# mainboard_v2_0.net
KiCad netlist of a schematic drawn in EAGLE
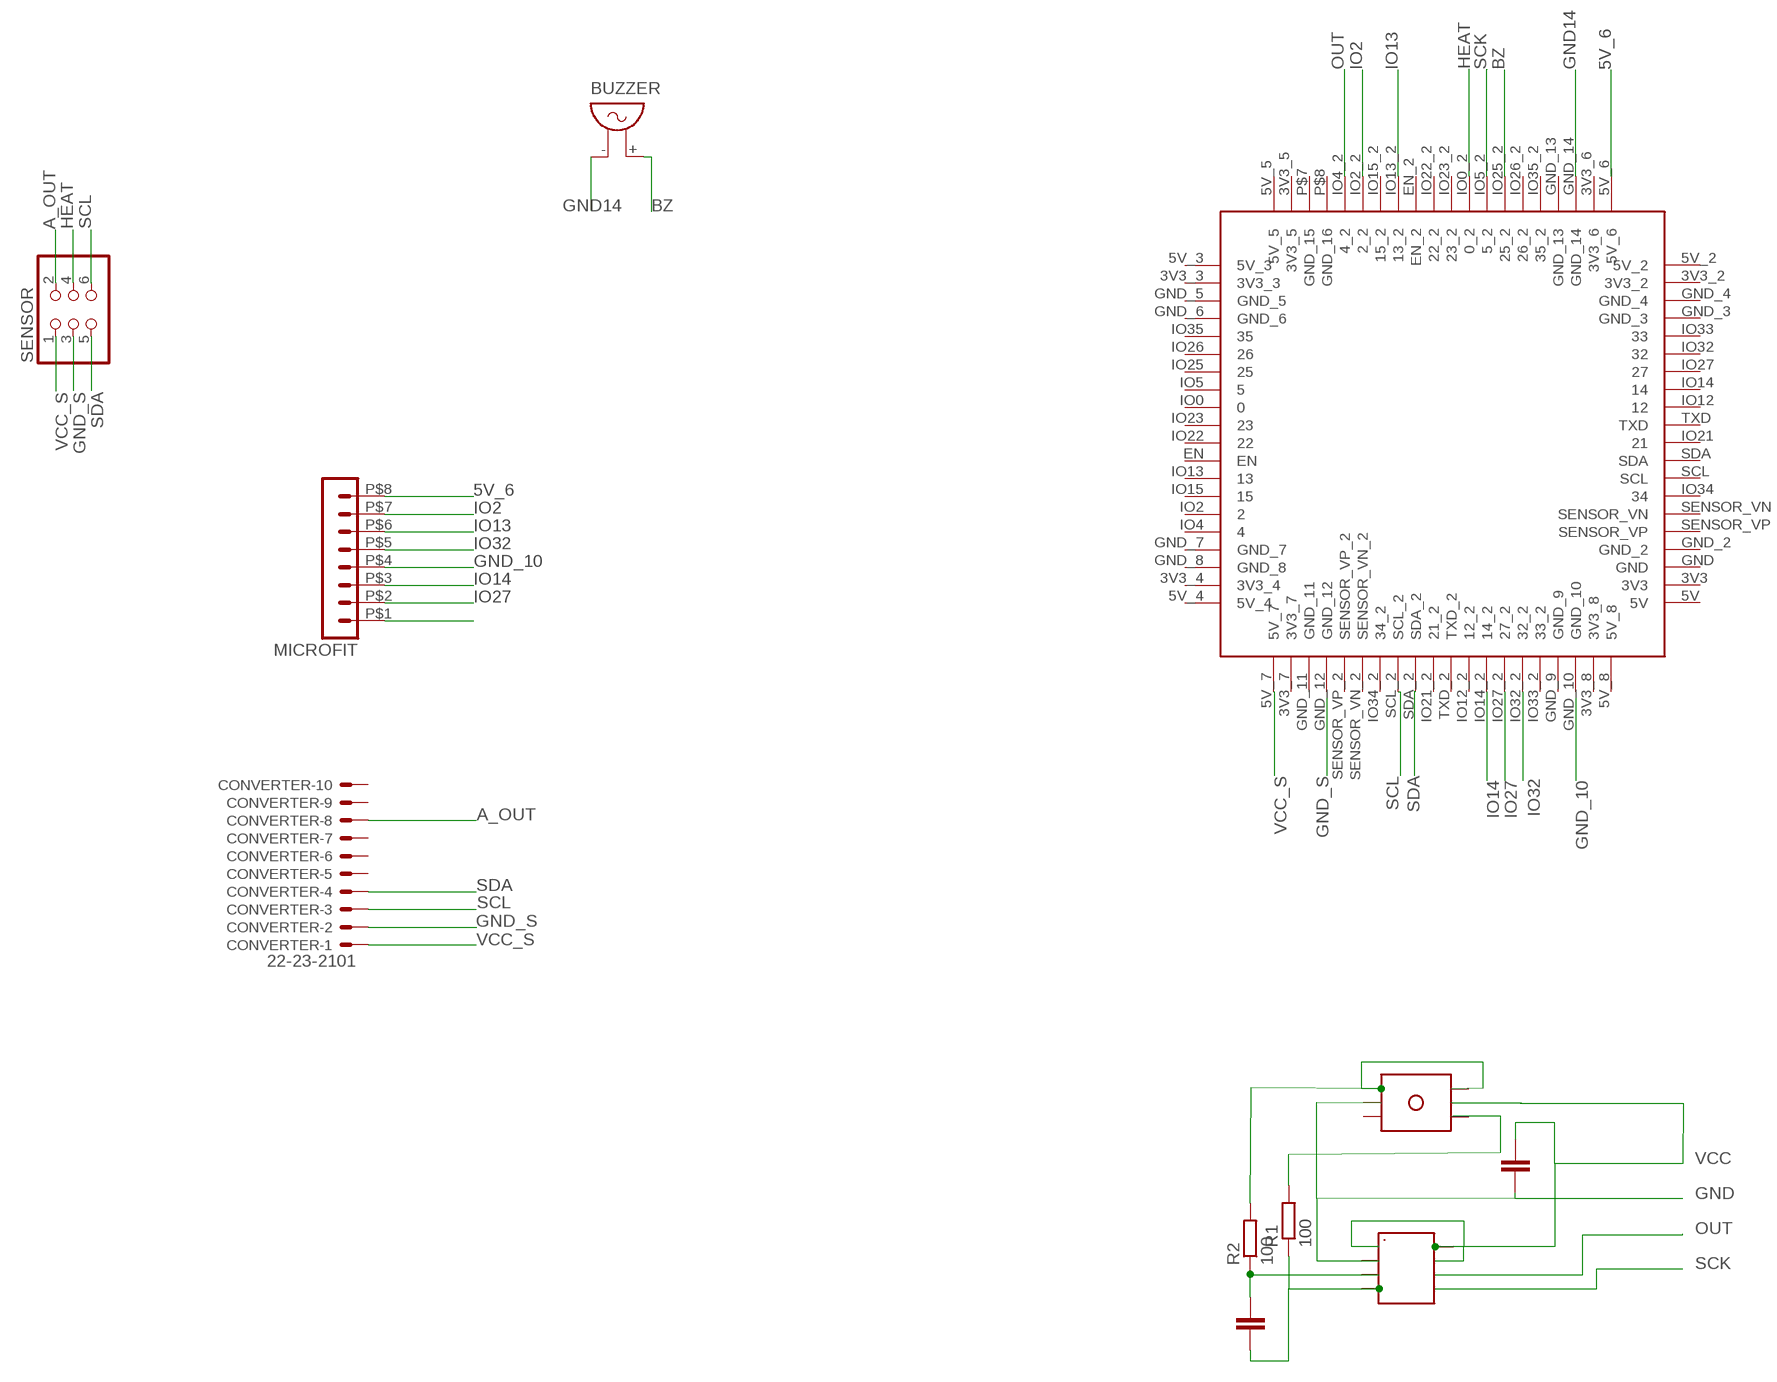
[diagram p0: schematic, sheet 1]

(export (version "E")
  (design (tool "Eeschema 10.0.6"))
  (components
    (comp (ref "BUZZER")
      (value "F/QMX")
      (footprint "eagle-import:F_QMX")
      (libsource (lib "eagle-import") (part "F/QMX"))
    )
    (comp (ref "C1")
      (value "100n")
      (footprint "eagle-import:C0805")
      (libsource (lib "eagle-import") (part "C-EUC0805"))
    )
    (comp (ref "C2")
      (value "100n")
      (footprint "eagle-import:C0805")
      (libsource (lib "eagle-import") (part "C-EUC0805"))
    )
    (comp (ref "CONVERTER")
      (value "22-23-2101")
      (footprint "eagle-import:22-23-2101")
      (fields (field (name "MF") "MOLEX"))
      (libsource (lib "eagle-import") (part "22-23-2101"))
    )
    (comp (ref "MICROFIT")
      (value "HEADER_POS8_43045-0800")
      (footprint "eagle-import:43045-0800")
      (libsource (lib "eagle-import") (part "HEADER_POS8_?43045-0800"))
    )
    (comp (ref "R1")
      (value "100")
      (footprint "eagle-import:R0805")
      (libsource (lib "eagle-import") (part "R-EU_R0805"))
    )
    (comp (ref "R2")
      (value "100")
      (footprint "eagle-import:R0805")
      (libsource (lib "eagle-import") (part "R-EU_R0805"))
    )
    (comp (ref "SENSOR")
      (value "PINHD-2X3")
      (footprint "eagle-import:2X03")
      (libsource (lib "eagle-import") (part "PINHD-2X3"))
    )
    (comp (ref "U$1")
      (value "WT32_SC01WT32_D")
      (footprint "eagle-import:WT32_DUPLICATED")
      (libsource (lib "eagle-import") (part "WT32_SC01WT32_D"))
    )
    (comp (ref "U$2")
      (value "HX710B")
      (footprint "eagle-import:HX710B_SMD")
      (libsource (lib "eagle-import") (part "HX710B"))
    )
    (comp (ref "U$3")
      (value "PRESSUREPRESSURE_PTH")
      (footprint "eagle-import:PRESSURE_PTH")
      (libsource (lib "eagle-import") (part "PRESSUREPRESSURE_PTH"))
    )
  )
  (nets
    (net (code "1") (name "/5V_6") (class "Default")
      (node (ref "MICROFIT") (pin "P$8") (pinfunction "8_P$8") (pintype "passive"))
      (node (ref "U$1") (pin "5V_6") (pinfunction "5V_6_5V_6") (pintype "bidirectional"))
    )
    (net (code "2") (name "/A_OUT") (class "Default")
      (node (ref "CONVERTER") (pin "8") (pinfunction "S_8") (pintype "passive"))
      (node (ref "SENSOR") (pin "2") (pinfunction "2_2") (pintype "passive"))
    )
    (net (code "3") (name "/BZ") (class "Default")
      (node (ref "BUZZER") (pin "+") (pinfunction "2_+") (pintype "passive"))
      (node (ref "U$1") (pin "IO25_2") (pinfunction "25_2_IO25_2") (pintype "bidirectional"))
    )
    (net (code "4") (name "/GND") (class "Default")
      (node (ref "C2") (pin "2") (pinfunction "2_2") (pintype "passive"))
      (node (ref "U$2") (pin "AGND") (pinfunction "AGND_AGND") (pintype "bidirectional"))
      (node (ref "U$3") (pin "2") (pinfunction "2_2") (pintype "bidirectional"))
    )
    (net (code "5") (name "/GND14") (class "Default")
      (node (ref "BUZZER") (pin "-") (pinfunction "1_-") (pintype "passive"))
      (node (ref "U$1") (pin "GND_14") (pinfunction "GND_14_GND_14") (pintype "bidirectional"))
    )
    (net (code "6") (name "/GND_10") (class "Default")
      (node (ref "MICROFIT") (pin "P$4") (pinfunction "4_P$4") (pintype "passive"))
      (node (ref "U$1") (pin "GND_10") (pinfunction "GND_10_GND_10") (pintype "bidirectional"))
    )
    (net (code "7") (name "/GND_S") (class "Default")
      (node (ref "CONVERTER") (pin "2") (pinfunction "S_2") (pintype "passive"))
      (node (ref "SENSOR") (pin "3") (pinfunction "3_3") (pintype "passive"))
      (node (ref "U$1") (pin "GND_12") (pinfunction "GND_12_GND_12") (pintype "bidirectional"))
    )
    (net (code "8") (name "/HEAT") (class "Default")
      (node (ref "SENSOR") (pin "4") (pinfunction "4_4") (pintype "passive"))
      (node (ref "U$1") (pin "IO0_2") (pinfunction "0_2_IO0_2") (pintype "bidirectional"))
    )
    (net (code "9") (name "/IO2") (class "Default")
      (node (ref "MICROFIT") (pin "P$7") (pinfunction "7_P$7") (pintype "passive"))
      (node (ref "U$1") (pin "IO2_2") (pinfunction "2_2_IO2_2") (pintype "bidirectional"))
    )
    (net (code "10") (name "/IO13") (class "Default")
      (node (ref "MICROFIT") (pin "P$6") (pinfunction "6_P$6") (pintype "passive"))
      (node (ref "U$1") (pin "IO13_2") (pinfunction "13_2_IO13_2") (pintype "bidirectional"))
    )
    (net (code "11") (name "/IO14") (class "Default")
      (node (ref "MICROFIT") (pin "P$3") (pinfunction "3_P$3") (pintype "passive"))
      (node (ref "U$1") (pin "IO14_2") (pinfunction "14_2_IO14_2") (pintype "bidirectional"))
    )
    (net (code "12") (name "/IO27") (class "Default")
      (node (ref "MICROFIT") (pin "P$2") (pinfunction "2_P$2") (pintype "passive"))
      (node (ref "U$1") (pin "IO27_2") (pinfunction "27_2_IO27_2") (pintype "bidirectional"))
    )
    (net (code "13") (name "/IO32") (class "Default")
      (node (ref "MICROFIT") (pin "P$5") (pinfunction "5_P$5") (pintype "passive"))
      (node (ref "U$1") (pin "IO32_2") (pinfunction "32_2_IO32_2") (pintype "bidirectional"))
    )
    (net (code "14") (name "/N$5") (class "Default")
      (node (ref "R1") (pin "2") (pinfunction "2_2") (pintype "passive"))
      (node (ref "U$3") (pin "4") (pinfunction "4_4") (pintype "bidirectional"))
    )
    (net (code "15") (name "/N$7") (class "Default")
      (node (ref "R2") (pin "2") (pinfunction "2_2") (pintype "passive"))
      (node (ref "U$3") (pin "1") (pinfunction "1_1") (pintype "bidirectional"))
      (node (ref "U$3") (pin "6") (pinfunction "6_6") (pintype "bidirectional"))
    )
    (net (code "16") (name "/OUT") (class "Default")
      (node (ref "U$1") (pin "IO4_2") (pinfunction "4_2_IO4_2") (pintype "bidirectional"))
      (node (ref "U$2") (pin "DOUT") (pinfunction "DOUT_DOUT") (pintype "bidirectional"))
    )
    (net (code "17") (name "/SCK") (class "Default")
      (node (ref "U$1") (pin "IO5_2") (pinfunction "5_2_IO5_2") (pintype "bidirectional"))
      (node (ref "U$2") (pin "SCK") (pinfunction "SCK_SCK") (pintype "bidirectional"))
    )
    (net (code "18") (name "/SCL") (class "Default")
      (node (ref "CONVERTER") (pin "3") (pinfunction "S_3") (pintype "passive"))
      (node (ref "SENSOR") (pin "6") (pinfunction "6_6") (pintype "passive"))
      (node (ref "U$1") (pin "SCL_2") (pinfunction "SCL_2_SCL_2") (pintype "bidirectional"))
    )
    (net (code "19") (name "/SDA") (class "Default")
      (node (ref "CONVERTER") (pin "4") (pinfunction "S_4") (pintype "passive"))
      (node (ref "SENSOR") (pin "5") (pinfunction "5_5") (pintype "passive"))
      (node (ref "U$1") (pin "SDA_2") (pinfunction "SDA_2_SDA_2") (pintype "bidirectional"))
    )
    (net (code "20") (name "/VCC") (class "Default")
      (node (ref "C2") (pin "1") (pinfunction "1_1") (pintype "passive"))
      (node (ref "U$2") (pin "AVDD") (pinfunction "AVDD_AVDD") (pintype "bidirectional"))
      (node (ref "U$2") (pin "DVDD") (pinfunction "DVDD_DVDD") (pintype "bidirectional"))
      (node (ref "U$2") (pin "VREF") (pinfunction "VREF_VREF") (pintype "bidirectional"))
      (node (ref "U$3") (pin "5") (pinfunction "5_5") (pintype "bidirectional"))
    )
    (net (code "21") (name "/VCC_S") (class "Default")
      (node (ref "CONVERTER") (pin "1") (pinfunction "S_1") (pintype "passive"))
      (node (ref "SENSOR") (pin "1") (pinfunction "1_1") (pintype "passive"))
      (node (ref "U$1") (pin "5V_7") (pinfunction "5V_7_5V_7") (pintype "bidirectional"))
    )
    (net (code "22") (name "Net-(C1-Pad1)") (class "Default")
      (node (ref "C1") (pin "1") (pinfunction "1_1") (pintype "passive"))
      (node (ref "R1") (pin "1") (pinfunction "1_1") (pintype "passive"))
      (node (ref "U$2") (pin "INP") (pinfunction "INP_INP") (pintype "bidirectional"))
    )
    (net (code "23") (name "Net-(C1-Pad2)") (class "Default")
      (node (ref "C1") (pin "2") (pinfunction "2_2") (pintype "passive"))
      (node (ref "R2") (pin "1") (pinfunction "1_1") (pintype "passive"))
      (node (ref "U$2") (pin "INN") (pinfunction "INN_INN") (pintype "bidirectional"))
    )
    (net (code "24") (name "unconnected-(CONVERTERB-S-Pad10)") (class "Default")
      (node (ref "CONVERTER") (pin "10") (pinfunction "S_10") (pintype "passive"))
    )
    (net (code "25") (name "unconnected-(CONVERTERF-S-Pad5)") (class "Default")
      (node (ref "CONVERTER") (pin "5") (pinfunction "S_5") (pintype "passive"))
    )
    (net (code "26") (name "unconnected-(CONVERTERG-S-Pad6)") (class "Default")
      (node (ref "CONVERTER") (pin "6") (pinfunction "S_6") (pintype "passive"))
    )
    (net (code "27") (name "unconnected-(CONVERTERH-S-Pad7)") (class "Default")
      (node (ref "CONVERTER") (pin "7") (pinfunction "S_7") (pintype "passive"))
    )
    (net (code "28") (name "unconnected-(CONVERTERJ-S-Pad9)") (class "Default")
      (node (ref "CONVERTER") (pin "9") (pinfunction "S_9") (pintype "passive"))
    )
    (net (code "29") (name "unconnected-(MICROFIT-1-PadP$1)") (class "Default")
      (node (ref "MICROFIT") (pin "P$1") (pinfunction "1_P$1") (pintype "passive"))
    )
    (net (code "30") (name "unconnected-(U$1-0-PadIO0)") (class "Default")
      (node (ref "U$1") (pin "IO0") (pinfunction "0_IO0") (pintype "bidirectional"))
    )
    (net (code "31") (name "unconnected-(U$1-2-PadIO2)") (class "Default")
      (node (ref "U$1") (pin "IO2") (pinfunction "2_IO2") (pintype "bidirectional"))
    )
    (net (code "32") (name "unconnected-(U$1-4-PadIO4)") (class "Default")
      (node (ref "U$1") (pin "IO4") (pinfunction "4_IO4") (pintype "bidirectional"))
    )
    (net (code "33") (name "unconnected-(U$1-5-PadIO5)") (class "Default")
      (node (ref "U$1") (pin "IO5") (pinfunction "5_IO5") (pintype "bidirectional"))
    )
    (net (code "34") (name "unconnected-(U$1-12-PadIO12)") (class "Default")
      (node (ref "U$1") (pin "IO12") (pinfunction "12_IO12") (pintype "bidirectional"))
    )
    (net (code "35") (name "unconnected-(U$1-12_2-PadIO12_2)") (class "Default")
      (node (ref "U$1") (pin "IO12_2") (pinfunction "12_2_IO12_2") (pintype "bidirectional"))
    )
    (net (code "36") (name "unconnected-(U$1-13-PadIO13)") (class "Default")
      (node (ref "U$1") (pin "IO13") (pinfunction "13_IO13") (pintype "bidirectional"))
    )
    (net (code "37") (name "unconnected-(U$1-14-PadIO14)") (class "Default")
      (node (ref "U$1") (pin "IO14") (pinfunction "14_IO14") (pintype "bidirectional"))
    )
    (net (code "38") (name "unconnected-(U$1-15-PadIO15)") (class "Default")
      (node (ref "U$1") (pin "IO15") (pinfunction "15_IO15") (pintype "bidirectional"))
    )
    (net (code "39") (name "unconnected-(U$1-15_2-PadIO15_2)") (class "Default")
      (node (ref "U$1") (pin "IO15_2") (pinfunction "15_2_IO15_2") (pintype "bidirectional"))
    )
    (net (code "40") (name "unconnected-(U$1-21-PadIO21)") (class "Default")
      (node (ref "U$1") (pin "IO21") (pinfunction "21_IO21") (pintype "bidirectional"))
    )
    (net (code "41") (name "unconnected-(U$1-21_2-PadIO21_2)") (class "Default")
      (node (ref "U$1") (pin "IO21_2") (pinfunction "21_2_IO21_2") (pintype "bidirectional"))
    )
    (net (code "42") (name "unconnected-(U$1-22-PadIO22)") (class "Default")
      (node (ref "U$1") (pin "IO22") (pinfunction "22_IO22") (pintype "bidirectional"))
    )
    (net (code "43") (name "unconnected-(U$1-22_2-PadIO22_2)") (class "Default")
      (node (ref "U$1") (pin "IO22_2") (pinfunction "22_2_IO22_2") (pintype "bidirectional"))
    )
    (net (code "44") (name "unconnected-(U$1-23-PadIO23)") (class "Default")
      (node (ref "U$1") (pin "IO23") (pinfunction "23_IO23") (pintype "bidirectional"))
    )
    (net (code "45") (name "unconnected-(U$1-23_2-PadIO23_2)") (class "Default")
      (node (ref "U$1") (pin "IO23_2") (pinfunction "23_2_IO23_2") (pintype "bidirectional"))
    )
    (net (code "46") (name "unconnected-(U$1-25-PadIO25)") (class "Default")
      (node (ref "U$1") (pin "IO25") (pinfunction "25_IO25") (pintype "bidirectional"))
    )
    (net (code "47") (name "unconnected-(U$1-26-PadIO26)") (class "Default")
      (node (ref "U$1") (pin "IO26") (pinfunction "26_IO26") (pintype "bidirectional"))
    )
    (net (code "48") (name "unconnected-(U$1-26_2-PadIO26_2)") (class "Default")
      (node (ref "U$1") (pin "IO26_2") (pinfunction "26_2_IO26_2") (pintype "bidirectional"))
    )
    (net (code "49") (name "unconnected-(U$1-27-PadIO27)") (class "Default")
      (node (ref "U$1") (pin "IO27") (pinfunction "27_IO27") (pintype "bidirectional"))
    )
    (net (code "50") (name "unconnected-(U$1-32-PadIO32)") (class "Default")
      (node (ref "U$1") (pin "IO32") (pinfunction "32_IO32") (pintype "bidirectional"))
    )
    (net (code "51") (name "unconnected-(U$1-33-PadIO33)") (class "Default")
      (node (ref "U$1") (pin "IO33") (pinfunction "33_IO33") (pintype "bidirectional"))
    )
    (net (code "52") (name "unconnected-(U$1-33_2-PadIO33_2)") (class "Default")
      (node (ref "U$1") (pin "IO33_2") (pinfunction "33_2_IO33_2") (pintype "bidirectional"))
    )
    (net (code "53") (name "unconnected-(U$1-34-PadIO34)") (class "Default")
      (node (ref "U$1") (pin "IO34") (pinfunction "34_IO34") (pintype "bidirectional"))
    )
    (net (code "54") (name "unconnected-(U$1-34_2-PadIO34_2)") (class "Default")
      (node (ref "U$1") (pin "IO34_2") (pinfunction "34_2_IO34_2") (pintype "bidirectional"))
    )
    (net (code "55") (name "unconnected-(U$1-35-PadIO35)") (class "Default")
      (node (ref "U$1") (pin "IO35") (pinfunction "35_IO35") (pintype "bidirectional"))
    )
    (net (code "56") (name "unconnected-(U$1-35_2-PadIO35_2)") (class "Default")
      (node (ref "U$1") (pin "IO35_2") (pinfunction "35_2_IO35_2") (pintype "bidirectional"))
    )
    (net (code "57") (name "unconnected-(U$1-GND_15-PadP$7)") (class "Default")
      (node (ref "U$1") (pin "P$7") (pinfunction "GND_15_P$7") (pintype "bidirectional"))
    )
    (net (code "58") (name "unconnected-(U$1-GND_16-PadP$8)") (class "Default")
      (node (ref "U$1") (pin "P$8") (pinfunction "GND_16_P$8") (pintype "bidirectional"))
    )
    (net (code "59") (name "unconnected-(U$1-Pad3V3)") (class "Default")
      (node (ref "U$1") (pin "3V3") (pinfunction "3V3_3V3") (pintype "bidirectional"))
    )
    (net (code "60") (name "unconnected-(U$1-Pad3V3_2)") (class "Default")
      (node (ref "U$1") (pin "3V3_2") (pinfunction "3V3_2_3V3_2") (pintype "bidirectional"))
    )
    (net (code "61") (name "unconnected-(U$1-Pad3V3_3)") (class "Default")
      (node (ref "U$1") (pin "3V3_3") (pinfunction "3V3_3_3V3_3") (pintype "bidirectional"))
    )
    (net (code "62") (name "unconnected-(U$1-Pad3V3_4)") (class "Default")
      (node (ref "U$1") (pin "3V3_4") (pinfunction "3V3_4_3V3_4") (pintype "bidirectional"))
    )
    (net (code "63") (name "unconnected-(U$1-Pad3V3_5)") (class "Default")
      (node (ref "U$1") (pin "3V3_5") (pinfunction "3V3_5_3V3_5") (pintype "bidirectional"))
    )
    (net (code "64") (name "unconnected-(U$1-Pad3V3_6)") (class "Default")
      (node (ref "U$1") (pin "3V3_6") (pinfunction "3V3_6_3V3_6") (pintype "bidirectional"))
    )
    (net (code "65") (name "unconnected-(U$1-Pad3V3_7)") (class "Default")
      (node (ref "U$1") (pin "3V3_7") (pinfunction "3V3_7_3V3_7") (pintype "bidirectional"))
    )
    (net (code "66") (name "unconnected-(U$1-Pad3V3_8)") (class "Default")
      (node (ref "U$1") (pin "3V3_8") (pinfunction "3V3_8_3V3_8") (pintype "bidirectional"))
    )
    (net (code "67") (name "unconnected-(U$1-Pad5V)") (class "Default")
      (node (ref "U$1") (pin "5V") (pinfunction "5V_5V") (pintype "bidirectional"))
    )
    (net (code "68") (name "unconnected-(U$1-Pad5V_2)") (class "Default")
      (node (ref "U$1") (pin "5V_2") (pinfunction "5V_2_5V_2") (pintype "bidirectional"))
    )
    (net (code "69") (name "unconnected-(U$1-Pad5V_3)") (class "Default")
      (node (ref "U$1") (pin "5V_3") (pinfunction "5V_3_5V_3") (pintype "bidirectional"))
    )
    (net (code "70") (name "unconnected-(U$1-Pad5V_4)") (class "Default")
      (node (ref "U$1") (pin "5V_4") (pinfunction "5V_4_5V_4") (pintype "bidirectional"))
    )
    (net (code "71") (name "unconnected-(U$1-Pad5V_5)") (class "Default")
      (node (ref "U$1") (pin "5V_5") (pinfunction "5V_5_5V_5") (pintype "bidirectional"))
    )
    (net (code "72") (name "unconnected-(U$1-Pad5V_8)") (class "Default")
      (node (ref "U$1") (pin "5V_8") (pinfunction "5V_8_5V_8") (pintype "bidirectional"))
    )
    (net (code "73") (name "unconnected-(U$1-PadEN)") (class "Default")
      (node (ref "U$1") (pin "EN") (pinfunction "EN_EN") (pintype "bidirectional"))
    )
    (net (code "74") (name "unconnected-(U$1-PadEN_2)") (class "Default")
      (node (ref "U$1") (pin "EN_2") (pinfunction "EN_2_EN_2") (pintype "bidirectional"))
    )
    (net (code "75") (name "unconnected-(U$1-PadGND)") (class "Default")
      (node (ref "U$1") (pin "GND") (pinfunction "GND_GND") (pintype "bidirectional"))
    )
    (net (code "76") (name "unconnected-(U$1-PadGND_2)") (class "Default")
      (node (ref "U$1") (pin "GND_2") (pinfunction "GND_2_GND_2") (pintype "bidirectional"))
    )
    (net (code "77") (name "unconnected-(U$1-PadGND_3)") (class "Default")
      (node (ref "U$1") (pin "GND_3") (pinfunction "GND_3_GND_3") (pintype "bidirectional"))
    )
    (net (code "78") (name "unconnected-(U$1-PadGND_4)") (class "Default")
      (node (ref "U$1") (pin "GND_4") (pinfunction "GND_4_GND_4") (pintype "bidirectional"))
    )
    (net (code "79") (name "unconnected-(U$1-PadGND_5)") (class "Default")
      (node (ref "U$1") (pin "GND_5") (pinfunction "GND_5_GND_5") (pintype "bidirectional"))
    )
    (net (code "80") (name "unconnected-(U$1-PadGND_6)") (class "Default")
      (node (ref "U$1") (pin "GND_6") (pinfunction "GND_6_GND_6") (pintype "bidirectional"))
    )
    (net (code "81") (name "unconnected-(U$1-PadGND_7)") (class "Default")
      (node (ref "U$1") (pin "GND_7") (pinfunction "GND_7_GND_7") (pintype "bidirectional"))
    )
    (net (code "82") (name "unconnected-(U$1-PadGND_8)") (class "Default")
      (node (ref "U$1") (pin "GND_8") (pinfunction "GND_8_GND_8") (pintype "bidirectional"))
    )
    (net (code "83") (name "unconnected-(U$1-PadGND_9)") (class "Default")
      (node (ref "U$1") (pin "GND_9") (pinfunction "GND_9_GND_9") (pintype "bidirectional"))
    )
    (net (code "84") (name "unconnected-(U$1-PadGND_11)") (class "Default")
      (node (ref "U$1") (pin "GND_11") (pinfunction "GND_11_GND_11") (pintype "bidirectional"))
    )
    (net (code "85") (name "unconnected-(U$1-PadGND_13)") (class "Default")
      (node (ref "U$1") (pin "GND_13") (pinfunction "GND_13_GND_13") (pintype "bidirectional"))
    )
    (net (code "86") (name "unconnected-(U$1-PadSCL)") (class "Default")
      (node (ref "U$1") (pin "SCL") (pinfunction "SCL_SCL") (pintype "bidirectional"))
    )
    (net (code "87") (name "unconnected-(U$1-PadSDA)") (class "Default")
      (node (ref "U$1") (pin "SDA") (pinfunction "SDA_SDA") (pintype "bidirectional"))
    )
    (net (code "88") (name "unconnected-(U$1-PadSENSOR_VN)") (class "Default")
      (node (ref "U$1") (pin "SENSOR_VN") (pinfunction "SENSOR_VN_SENSOR_VN") (pintype "bidirectional"))
    )
    (net (code "89") (name "unconnected-(U$1-PadSENSOR_VN_2)") (class "Default")
      (node (ref "U$1") (pin "SENSOR_VN_2") (pinfunction "SENSOR_VN_2_SENSOR_VN_2") (pintype "bidirectional"))
    )
    (net (code "90") (name "unconnected-(U$1-PadSENSOR_VP)") (class "Default")
      (node (ref "U$1") (pin "SENSOR_VP") (pinfunction "SENSOR_VP_SENSOR_VP") (pintype "bidirectional"))
    )
    (net (code "91") (name "unconnected-(U$1-PadSENSOR_VP_2)") (class "Default")
      (node (ref "U$1") (pin "SENSOR_VP_2") (pinfunction "SENSOR_VP_2_SENSOR_VP_2") (pintype "bidirectional"))
    )
    (net (code "92") (name "unconnected-(U$1-PadTXD)") (class "Default")
      (node (ref "U$1") (pin "TXD") (pinfunction "TXD_TXD") (pintype "bidirectional"))
    )
    (net (code "93") (name "unconnected-(U$1-PadTXD_2)") (class "Default")
      (node (ref "U$1") (pin "TXD_2") (pinfunction "TXD_2_TXD_2") (pintype "bidirectional"))
    )
    (net (code "94") (name "unconnected-(U$3-Pad3)") (class "Default")
      (node (ref "U$3") (pin "3") (pinfunction "3_3") (pintype "bidirectional"))
    )
  )
)
